# usbtiny.net
KiCad netlist of a schematic drawn in EAGLE
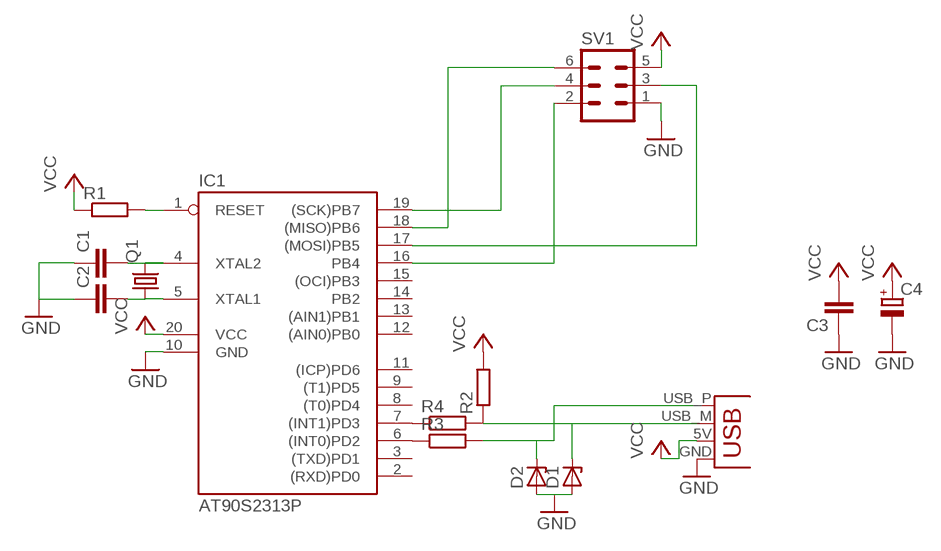
[diagram p0: schematic, sheet 1]

(export (version "E")
  (design (tool "Eeschema 10.0.6"))
  (components
    (comp (ref "C1")
      (value "C-EU025-025X050")
      (footprint "eagle-import:C025-025X050")
      (libsource (lib "eagle-import") (part "C-EU025-025X050"))
    )
    (comp (ref "C2")
      (value "C-EU025-025X050")
      (footprint "eagle-import:C025-025X050")
      (libsource (lib "eagle-import") (part "C-EU025-025X050"))
    )
    (comp (ref "C3")
      (value "C-EU025-025X050")
      (footprint "eagle-import:C025-025X050")
      (libsource (lib "eagle-import") (part "C-EU025-025X050"))
    )
    (comp (ref "C4")
      (value "CPOL-EUE2.5-6")
      (footprint "eagle-import:E2,5-6")
      (libsource (lib "eagle-import") (part "CPOL-EUE2.5-6"))
    )
    (comp (ref "D1")
      (value "ZENER-DIODEDO35Z10")
      (footprint "eagle-import:DO35Z10")
      (libsource (lib "eagle-import") (part "ZENER-DIODEDO35Z10"))
    )
    (comp (ref "D2")
      (value "ZENER-DIODEDO35Z10")
      (footprint "eagle-import:DO35Z10")
      (libsource (lib "eagle-import") (part "ZENER-DIODEDO35Z10"))
    )
    (comp (ref "IC1")
      (value "AT90S2313P")
      (footprint "eagle-import:DIL20")
      (libsource (lib "eagle-import") (part "AT90S2313P"))
    )
    (comp (ref "JP2")
      (value "USBPCB")
      (footprint "eagle-import:USB-A-PCB")
      (libsource (lib "eagle-import") (part "USBPCB"))
    )
    (comp (ref "Q1")
      (value "CRYSTALHC49U70")
      (footprint "eagle-import:HC49U70")
      (libsource (lib "eagle-import") (part "CRYSTALHC49U70"))
    )
    (comp (ref "R1")
      (value "R-EU_0207/10")
      (footprint "eagle-import:0207_10")
      (libsource (lib "eagle-import") (part "R-EU_0207/10"))
    )
    (comp (ref "R2")
      (value "R-EU_0207/10")
      (footprint "eagle-import:0207_10")
      (libsource (lib "eagle-import") (part "R-EU_0207/10"))
    )
    (comp (ref "R3")
      (value "R-EU_0207/10")
      (footprint "eagle-import:0207_10")
      (libsource (lib "eagle-import") (part "R-EU_0207/10"))
    )
    (comp (ref "R4")
      (value "R-EU_0207/10")
      (footprint "eagle-import:0207_10")
      (libsource (lib "eagle-import") (part "R-EU_0207/10"))
    )
    (comp (ref "SV1")
      (value "MA03-2")
      (footprint "eagle-import:MA03-2")
      (libsource (lib "eagle-import") (part "MA03-2"))
    )
  )
  (nets
    (net (code "1") (name "GND") (class "Default")
      (node (ref "C1") (pin "1") (pinfunction "1_1") (pintype "passive"))
      (node (ref "C2") (pin "1") (pinfunction "1_1") (pintype "passive"))
      (node (ref "C3") (pin "1") (pinfunction "1_1") (pintype "passive"))
      (node (ref "C4") (pin "-") (pinfunction "-_-") (pintype "passive"))
      (node (ref "D1") (pin "A") (pinfunction "A_A") (pintype "passive"))
      (node (ref "D2") (pin "A") (pinfunction "A_A") (pintype "passive"))
      (node (ref "IC1") (pin "10") (pinfunction "GND_10") (pintype "power_in"))
      (node (ref "JP2") (pin "GND") (pinfunction "GND_GND") (pintype "bidirectional"))
      (node (ref "SV1") (pin "1") (pinfunction "1_1") (pintype "passive"))
    )
    (net (code "2") (name "Net-(IC1-(INT0)PD2)") (class "Default")
      (node (ref "IC1") (pin "6") (pinfunction "(INT0)PD2_6") (pintype "bidirectional"))
      (node (ref "R3") (pin "1") (pinfunction "1_1") (pintype "passive"))
    )
    (net (code "3") (name "Net-(IC1-(INT1)PD3)") (class "Default")
      (node (ref "IC1") (pin "7") (pinfunction "(INT1)PD3_7") (pintype "bidirectional"))
      (node (ref "R4") (pin "1") (pinfunction "1_1") (pintype "passive"))
    )
    (net (code "4") (name "Net-(IC1-(MISO)PB6)") (class "Default")
      (node (ref "IC1") (pin "18") (pinfunction "(MISO)PB6_18") (pintype "bidirectional"))
      (node (ref "SV1") (pin "6") (pinfunction "6_6") (pintype "passive"))
    )
    (net (code "5") (name "Net-(IC1-(MOSI)PB5)") (class "Default")
      (node (ref "IC1") (pin "17") (pinfunction "(MOSI)PB5_17") (pintype "bidirectional"))
      (node (ref "SV1") (pin "3") (pinfunction "3_3") (pintype "passive"))
    )
    (net (code "6") (name "Net-(IC1-(SCK)PB7)") (class "Default")
      (node (ref "IC1") (pin "19") (pinfunction "(SCK)PB7_19") (pintype "bidirectional"))
      (node (ref "SV1") (pin "4") (pinfunction "4_4") (pintype "passive"))
    )
    (net (code "7") (name "Net-(IC1-PB4)") (class "Default")
      (node (ref "IC1") (pin "16") (pinfunction "PB4_16") (pintype "bidirectional"))
      (node (ref "SV1") (pin "2") (pinfunction "2_2") (pintype "passive"))
    )
    (net (code "8") (name "Net-(IC1-RESET)") (class "Default")
      (node (ref "IC1") (pin "1") (pinfunction "RESET_1") (pintype "bidirectional"))
      (node (ref "R1") (pin "2") (pinfunction "2_2") (pintype "passive"))
    )
    (net (code "9") (name "Net-(IC1-XTAL1)") (class "Default")
      (node (ref "C2") (pin "2") (pinfunction "2_2") (pintype "passive"))
      (node (ref "IC1") (pin "5") (pinfunction "XTAL1_5") (pintype "bidirectional"))
      (node (ref "Q1") (pin "1") (pinfunction "1_1") (pintype "passive"))
    )
    (net (code "10") (name "Net-(IC1-XTAL2)") (class "Default")
      (node (ref "C1") (pin "2") (pinfunction "2_2") (pintype "passive"))
      (node (ref "IC1") (pin "4") (pinfunction "XTAL2_4") (pintype "bidirectional"))
      (node (ref "Q1") (pin "2") (pinfunction "2_2") (pintype "passive"))
    )
    (net (code "11") (name "Net-(JP2-D+)") (class "Default")
      (node (ref "D2") (pin "C") (pinfunction "C_C") (pintype "passive"))
      (node (ref "JP2") (pin "USB_P") (pinfunction "D+_USB_P") (pintype "bidirectional"))
      (node (ref "R3") (pin "2") (pinfunction "2_2") (pintype "passive"))
    )
    (net (code "12") (name "Net-(JP2-D-)") (class "Default")
      (node (ref "D1") (pin "C") (pinfunction "C_C") (pintype "passive"))
      (node (ref "JP2") (pin "USB_M") (pinfunction "D-_USB_M") (pintype "bidirectional"))
      (node (ref "R2") (pin "1") (pinfunction "1_1") (pintype "passive"))
      (node (ref "R4") (pin "2") (pinfunction "2_2") (pintype "passive"))
    )
    (net (code "13") (name "VCC") (class "Default")
      (node (ref "C3") (pin "2") (pinfunction "2_2") (pintype "passive"))
      (node (ref "C4") (pin "+") (pinfunction "+_+") (pintype "passive"))
      (node (ref "IC1") (pin "20") (pinfunction "VCC_20") (pintype "power_in"))
      (node (ref "JP2") (pin "5V") (pinfunction "VBUS_5V") (pintype "bidirectional"))
      (node (ref "R1") (pin "1") (pinfunction "1_1") (pintype "passive"))
      (node (ref "R2") (pin "2") (pinfunction "2_2") (pintype "passive"))
      (node (ref "SV1") (pin "5") (pinfunction "5_5") (pintype "passive"))
    )
    (net (code "14") (name "unconnected-(IC1-(AIN0)PB0-Pad12)") (class "Default")
      (node (ref "IC1") (pin "12") (pinfunction "(AIN0)PB0_12") (pintype "bidirectional"))
    )
    (net (code "15") (name "unconnected-(IC1-(AIN1)PB1-Pad13)") (class "Default")
      (node (ref "IC1") (pin "13") (pinfunction "(AIN1)PB1_13") (pintype "bidirectional"))
    )
    (net (code "16") (name "unconnected-(IC1-(ICP)PD6-Pad11)") (class "Default")
      (node (ref "IC1") (pin "11") (pinfunction "(ICP)PD6_11") (pintype "bidirectional"))
    )
    (net (code "17") (name "unconnected-(IC1-(OCI)PB3-Pad15)") (class "Default")
      (node (ref "IC1") (pin "15") (pinfunction "(OCI)PB3_15") (pintype "bidirectional"))
    )
    (net (code "18") (name "unconnected-(IC1-(RXD)PD0-Pad2)") (class "Default")
      (node (ref "IC1") (pin "2") (pinfunction "(RXD)PD0_2") (pintype "bidirectional"))
    )
    (net (code "19") (name "unconnected-(IC1-(T0)PD4-Pad8)") (class "Default")
      (node (ref "IC1") (pin "8") (pinfunction "(T0)PD4_8") (pintype "bidirectional"))
    )
    (net (code "20") (name "unconnected-(IC1-(T1)PD5-Pad9)") (class "Default")
      (node (ref "IC1") (pin "9") (pinfunction "(T1)PD5_9") (pintype "bidirectional"))
    )
    (net (code "21") (name "unconnected-(IC1-(TXD)PD1-Pad3)") (class "Default")
      (node (ref "IC1") (pin "3") (pinfunction "(TXD)PD1_3") (pintype "bidirectional"))
    )
    (net (code "22") (name "unconnected-(IC1-PB2-Pad14)") (class "Default")
      (node (ref "IC1") (pin "14") (pinfunction "PB2_14") (pintype "bidirectional"))
    )
  )
)
